# GeisaBoard.net
KiCad netlist of a schematic drawn in EAGLE
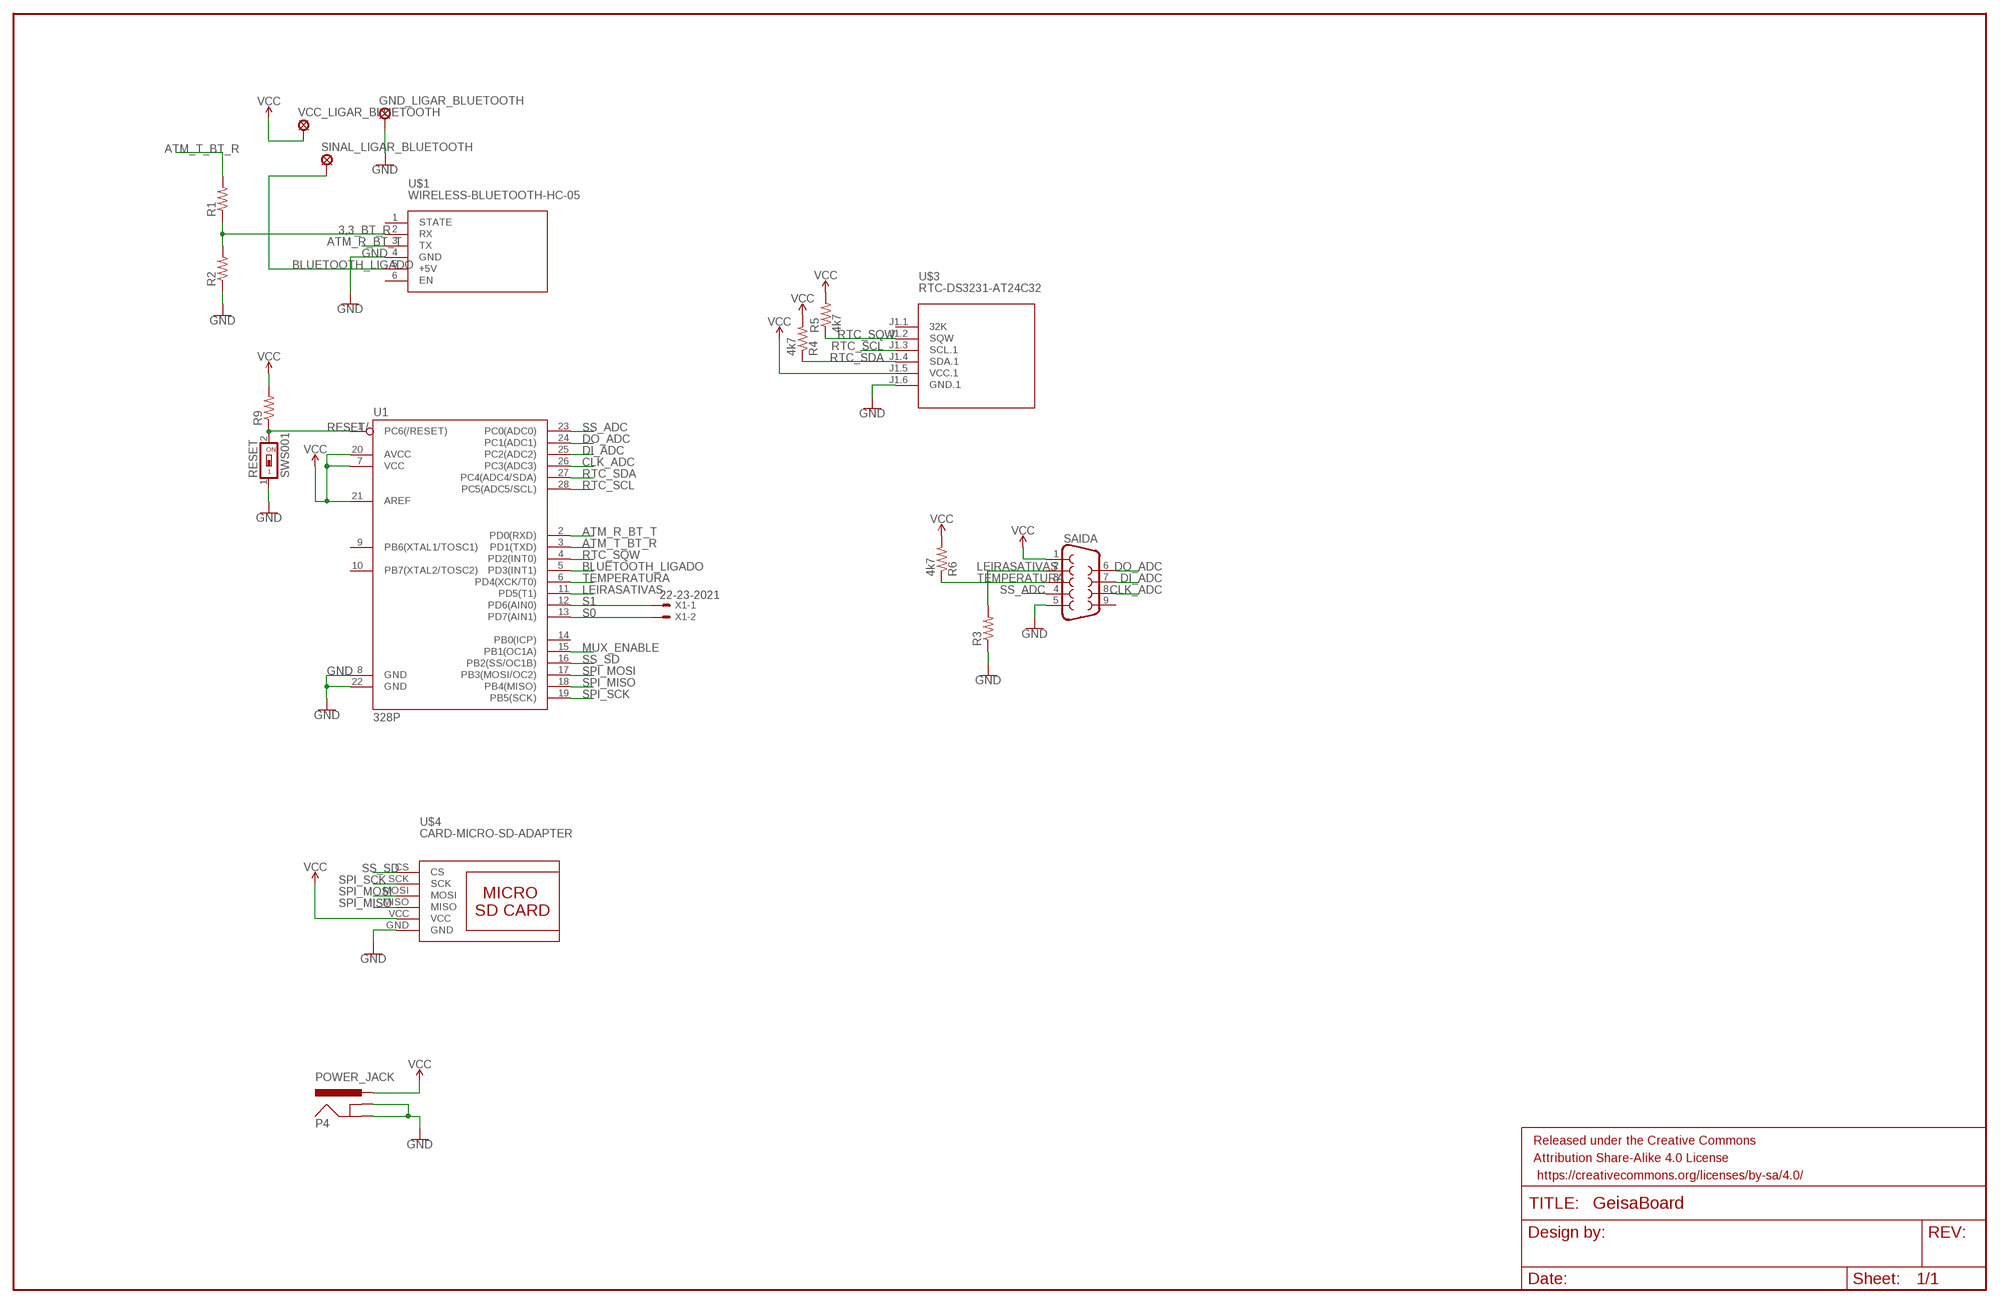
[diagram p0: schematic, sheet 1]

(export (version "E")
  (design (tool "Eeschema 10.0.6"))
  (components
    (comp (ref "FRAME1")
      (value "FRAME-LEDGER")
      (footprint "eagle-import:CREATIVE_COMMONS")
      (libsource (lib "eagle-import") (part "FRAME-LEDGER"))
    )
    (comp (ref "GND_LIGAR_BLUETOOTH")
      (value "LSP11")
      (footprint "eagle-import:LSP11")
      (libsource (lib "eagle-import") (part "LSP11"))
    )
    (comp (ref "P4")
      (value "POWER_JACK")
      (footprint "eagle-import:POWER_JACK_PTH")
      (libsource (lib "eagle-import") (part "POWER_JACK"))
    )
    (comp (ref "R1")
      (value "R-US_0204/7")
      (footprint "eagle-import:0204_7")
      (libsource (lib "eagle-import") (part "R-US_0204/7"))
    )
    (comp (ref "R2")
      (value "R-US_0204/7")
      (footprint "eagle-import:0204_7")
      (libsource (lib "eagle-import") (part "R-US_0204/7"))
    )
    (comp (ref "R3")
      (value "R-US_0204/7")
      (footprint "eagle-import:0204_7")
      (libsource (lib "eagle-import") (part "R-US_0204/7"))
    )
    (comp (ref "R4")
      (value "4k7")
      (footprint "eagle-import:0204_7")
      (libsource (lib "eagle-import") (part "R-US_0204/7"))
    )
    (comp (ref "R5")
      (value "4k7")
      (footprint "eagle-import:0204_7")
      (libsource (lib "eagle-import") (part "R-US_0204/7"))
    )
    (comp (ref "R6")
      (value "4k7")
      (footprint "eagle-import:0204_7")
      (libsource (lib "eagle-import") (part "R-US_0204/7"))
    )
    (comp (ref "R9")
      (value "R-US_0204/7")
      (footprint "eagle-import:0204_7")
      (libsource (lib "eagle-import") (part "R-US_0204/7"))
    )
    (comp (ref "RESET")
      (value "SWS001")
      (footprint "eagle-import:SMS-001")
      (libsource (lib "eagle-import") (part "SWS001"))
    )
    (comp (ref "SAIDA")
      (value "DB9FEMALE")
      (footprint "eagle-import:DB9")
      (libsource (lib "eagle-import") (part "DB9FEMALE"))
    )
    (comp (ref "SINAL_LIGAR_BLUETOOTH")
      (value "LSP11")
      (footprint "eagle-import:LSP11")
      (libsource (lib "eagle-import") (part "LSP11"))
    )
    (comp (ref "U$1")
      (value "WIRELESS-BLUETOOTH-HC-05")
      (footprint "eagle-import:WIRELESS-BLUETOOTH-HC-05")
      (libsource (lib "eagle-import") (part "WIRELESS-BLUETOOTH-HC-05"))
    )
    (comp (ref "U$3")
      (value "RTC-DS3231-AT24C32")
      (footprint "eagle-import:RTC-DS3231-AT24C32")
      (libsource (lib "eagle-import") (part "RTC-DS3231-AT24C32"))
    )
    (comp (ref "U$4")
      (value "CARD-MICRO-SD-ADAPTER")
      (footprint "eagle-import:CARD-MICRO-SD-ADAPTER")
      (libsource (lib "eagle-import") (part "CARD-MICRO-SD-ADAPTER"))
    )
    (comp (ref "U1")
      (value "328P")
      (footprint "eagle-import:DIP28")
      (libsource (lib "eagle-import") (part "ATMEGA328P_PDIP"))
    )
    (comp (ref "VCC_LIGAR_BLUETOOTH")
      (value "LSP11")
      (footprint "eagle-import:LSP11")
      (libsource (lib "eagle-import") (part "LSP11"))
    )
    (comp (ref "X1")
      (value "22-23-2021")
      (footprint "eagle-import:22-23-2021")
      (fields (field (name "MF") "MOLEX"))
      (libsource (lib "eagle-import") (part "22-23-2021"))
    )
  )
  (nets
    (net (code "1") (name "/3,3_BT_R") (class "Default")
      (node (ref "R1") (pin "1") (pinfunction "1_1") (pintype "passive"))
      (node (ref "R2") (pin "2") (pinfunction "2_2") (pintype "passive"))
      (node (ref "U$1") (pin "2") (pinfunction "RX_2") (pintype "bidirectional"))
    )
    (net (code "2") (name "/ATM_R_BT_T") (class "Default")
      (node (ref "U$1") (pin "3") (pinfunction "TX_3") (pintype "bidirectional"))
      (node (ref "U1") (pin "2") (pinfunction "PD0(RXD)_2") (pintype "bidirectional"))
    )
    (net (code "3") (name "/ATM_T_BT_R") (class "Default")
      (node (ref "R1") (pin "2") (pinfunction "2_2") (pintype "passive"))
      (node (ref "U1") (pin "3") (pinfunction "PD1(TXD)_3") (pintype "bidirectional"))
    )
    (net (code "4") (name "/BLUETOOTH_LIGADO") (class "Default")
      (node (ref "SINAL_LIGAR_BLUETOOTH") (pin "MP") (pinfunction "MP_MP") (pintype "passive"))
      (node (ref "U$1") (pin "5") (pinfunction "+5V_5") (pintype "power_in"))
      (node (ref "U1") (pin "5") (pinfunction "PD3(INT1)_5") (pintype "bidirectional"))
    )
    (net (code "5") (name "/CLK_ADC") (class "Default")
      (node (ref "SAIDA") (pin "8") (pinfunction "8_8") (pintype "passive"))
      (node (ref "U1") (pin "26") (pinfunction "PC3(ADC3)_26") (pintype "bidirectional"))
    )
    (net (code "6") (name "/DI_ADC") (class "Default")
      (node (ref "SAIDA") (pin "7") (pinfunction "7_7") (pintype "passive"))
      (node (ref "U1") (pin "25") (pinfunction "PC2(ADC2)_25") (pintype "bidirectional"))
    )
    (net (code "7") (name "/DO_ADC") (class "Default")
      (node (ref "SAIDA") (pin "6") (pinfunction "6_6") (pintype "passive"))
      (node (ref "U1") (pin "24") (pinfunction "PC1(ADC1)_24") (pintype "bidirectional"))
    )
    (net (code "8") (name "/LEIRASATIVAS") (class "Default")
      (node (ref "R3") (pin "2") (pinfunction "2_2") (pintype "passive"))
      (node (ref "SAIDA") (pin "2") (pinfunction "2_2") (pintype "passive"))
      (node (ref "U1") (pin "11") (pinfunction "PD5(T1)_11") (pintype "bidirectional"))
    )
    (net (code "9") (name "/MUX_ENABLE") (class "Default")
      (node (ref "U1") (pin "15") (pinfunction "PB1(OC1A)_15") (pintype "bidirectional"))
    )
    (net (code "10") (name "/RESET{slash}") (class "Default")
      (node (ref "R9") (pin "1") (pinfunction "1_1") (pintype "passive"))
      (node (ref "RESET") (pin "2") (pinfunction "2_2") (pintype "passive"))
      (node (ref "U1") (pin "1") (pinfunction "PC6(/RESET)_1") (pintype "bidirectional"))
    )
    (net (code "11") (name "/RTC_SCL") (class "Default")
      (node (ref "U$3") (pin "J1.3") (pinfunction "SCL.1_J1.3") (pintype "bidirectional"))
      (node (ref "U1") (pin "28") (pinfunction "PC5(ADC5/SCL)_28") (pintype "bidirectional"))
    )
    (net (code "12") (name "/RTC_SDA") (class "Default")
      (node (ref "R4") (pin "1") (pinfunction "1_1") (pintype "passive"))
      (node (ref "U$3") (pin "J1.4") (pinfunction "SDA.1_J1.4") (pintype "bidirectional"))
      (node (ref "U1") (pin "27") (pinfunction "PC4(ADC4/SDA)_27") (pintype "bidirectional"))
    )
    (net (code "13") (name "/RTC_SQW") (class "Default")
      (node (ref "R5") (pin "1") (pinfunction "1_1") (pintype "passive"))
      (node (ref "U$3") (pin "J1.2") (pinfunction "SQW_J1.2") (pintype "bidirectional"))
      (node (ref "U1") (pin "4") (pinfunction "PD2(INT0)_4") (pintype "bidirectional"))
    )
    (net (code "14") (name "/S0") (class "Default")
      (node (ref "U1") (pin "13") (pinfunction "PD7(AIN1)_13") (pintype "bidirectional"))
      (node (ref "X1") (pin "2") (pinfunction "S_2") (pintype "passive"))
    )
    (net (code "15") (name "/S1") (class "Default")
      (node (ref "U1") (pin "12") (pinfunction "PD6(AIN0)_12") (pintype "bidirectional"))
      (node (ref "X1") (pin "1") (pinfunction "S_1") (pintype "passive"))
    )
    (net (code "16") (name "/SPI_MISO") (class "Default")
      (node (ref "U$4") (pin "MISO") (pinfunction "MISO_MISO") (pintype "bidirectional"))
      (node (ref "U1") (pin "18") (pinfunction "PB4(MISO)_18") (pintype "bidirectional"))
    )
    (net (code "17") (name "/SPI_MOSI") (class "Default")
      (node (ref "U$4") (pin "MOSI") (pinfunction "MOSI_MOSI") (pintype "bidirectional"))
      (node (ref "U1") (pin "17") (pinfunction "PB3(MOSI/OC2)_17") (pintype "bidirectional"))
    )
    (net (code "18") (name "/SPI_SCK") (class "Default")
      (node (ref "U$4") (pin "SCK") (pinfunction "SCK_SCK") (pintype "bidirectional"))
      (node (ref "U1") (pin "19") (pinfunction "PB5(SCK)_19") (pintype "bidirectional"))
    )
    (net (code "19") (name "/SS_ADC") (class "Default")
      (node (ref "SAIDA") (pin "4") (pinfunction "4_4") (pintype "passive"))
      (node (ref "U1") (pin "23") (pinfunction "PC0(ADC0)_23") (pintype "bidirectional"))
    )
    (net (code "20") (name "/SS_SD") (class "Default")
      (node (ref "U$4") (pin "CS") (pinfunction "CS_CS") (pintype "bidirectional"))
      (node (ref "U1") (pin "16") (pinfunction "PB2(SS/OC1B)_16") (pintype "bidirectional"))
    )
    (net (code "21") (name "/TEMPERATURA") (class "Default")
      (node (ref "R6") (pin "1") (pinfunction "1_1") (pintype "passive"))
      (node (ref "SAIDA") (pin "3") (pinfunction "3_3") (pintype "passive"))
      (node (ref "U1") (pin "6") (pinfunction "PD4(XCK/T0)_6") (pintype "bidirectional"))
    )
    (net (code "22") (name "GND") (class "Default")
      (node (ref "GND_LIGAR_BLUETOOTH") (pin "MP") (pinfunction "MP_MP") (pintype "passive"))
      (node (ref "P4") (pin "GND") (pinfunction "GND_GND") (pintype "bidirectional"))
      (node (ref "P4") (pin "GNDBREAK") (pinfunction "GNDBREAK_GNDBREAK") (pintype "bidirectional"))
      (node (ref "R2") (pin "1") (pinfunction "1_1") (pintype "passive"))
      (node (ref "R3") (pin "1") (pinfunction "1_1") (pintype "passive"))
      (node (ref "RESET") (pin "1") (pinfunction "1_1") (pintype "passive"))
      (node (ref "SAIDA") (pin "5") (pinfunction "5_5") (pintype "passive"))
      (node (ref "U$1") (pin "4") (pinfunction "GND_4") (pintype "power_in"))
      (node (ref "U$3") (pin "J1.6") (pinfunction "GND.1_J1.6") (pintype "power_in"))
      (node (ref "U$4") (pin "GND") (pinfunction "GND_GND") (pintype "power_in"))
      (node (ref "U1") (pin "22") (pinfunction "GND_22") (pintype "bidirectional"))
      (node (ref "U1") (pin "8") (pinfunction "GND_8") (pintype "bidirectional"))
    )
    (net (code "23") (name "VCC") (class "Default")
      (node (ref "P4") (pin "PWR") (pinfunction "PWR_PWR") (pintype "bidirectional"))
      (node (ref "R4") (pin "2") (pinfunction "2_2") (pintype "passive"))
      (node (ref "R5") (pin "2") (pinfunction "2_2") (pintype "passive"))
      (node (ref "R6") (pin "2") (pinfunction "2_2") (pintype "passive"))
      (node (ref "R9") (pin "2") (pinfunction "2_2") (pintype "passive"))
      (node (ref "SAIDA") (pin "1") (pinfunction "1_1") (pintype "passive"))
      (node (ref "U$3") (pin "J1.5") (pinfunction "VCC.1_J1.5") (pintype "power_in"))
      (node (ref "U$4") (pin "VCC") (pinfunction "VCC_VCC") (pintype "power_in"))
      (node (ref "U1") (pin "20") (pinfunction "AVCC_20") (pintype "bidirectional"))
      (node (ref "U1") (pin "21") (pinfunction "AREF_21") (pintype "bidirectional"))
      (node (ref "U1") (pin "7") (pinfunction "VCC_7") (pintype "bidirectional"))
      (node (ref "VCC_LIGAR_BLUETOOTH") (pin "MP") (pinfunction "MP_MP") (pintype "passive"))
    )
    (net (code "24") (name "unconnected-(SAIDA-Pad9)") (class "Default")
      (node (ref "SAIDA") (pin "9") (pinfunction "9_9") (pintype "passive"))
    )
    (net (code "25") (name "unconnected-(U$1-EN-Pad6)") (class "Default")
      (node (ref "U$1") (pin "6") (pinfunction "EN_6") (pintype "bidirectional"))
    )
    (net (code "26") (name "unconnected-(U$1-STATE-Pad1)") (class "Default")
      (node (ref "U$1") (pin "1") (pinfunction "STATE_1") (pintype "bidirectional"))
    )
    (net (code "27") (name "unconnected-(U$3-32K-PadJ1.1)") (class "Default")
      (node (ref "U$3") (pin "J1.1") (pinfunction "32K_J1.1") (pintype "bidirectional"))
    )
    (net (code "28") (name "unconnected-(U1-PB0(ICP)-Pad14)") (class "Default")
      (node (ref "U1") (pin "14") (pinfunction "PB0(ICP)_14") (pintype "bidirectional"))
    )
    (net (code "29") (name "unconnected-(U1-PB6(XTAL1{slash}TOSC1)-Pad9)") (class "Default")
      (node (ref "U1") (pin "9") (pinfunction "PB6(XTAL1/TOSC1)_9") (pintype "bidirectional"))
    )
    (net (code "30") (name "unconnected-(U1-PB7(XTAL2{slash}TOSC2)-Pad10)") (class "Default")
      (node (ref "U1") (pin "10") (pinfunction "PB7(XTAL2/TOSC2)_10") (pintype "bidirectional"))
    )
  )
)
